# on_protoboard.net
KiCad netlist of a schematic drawn in EAGLE
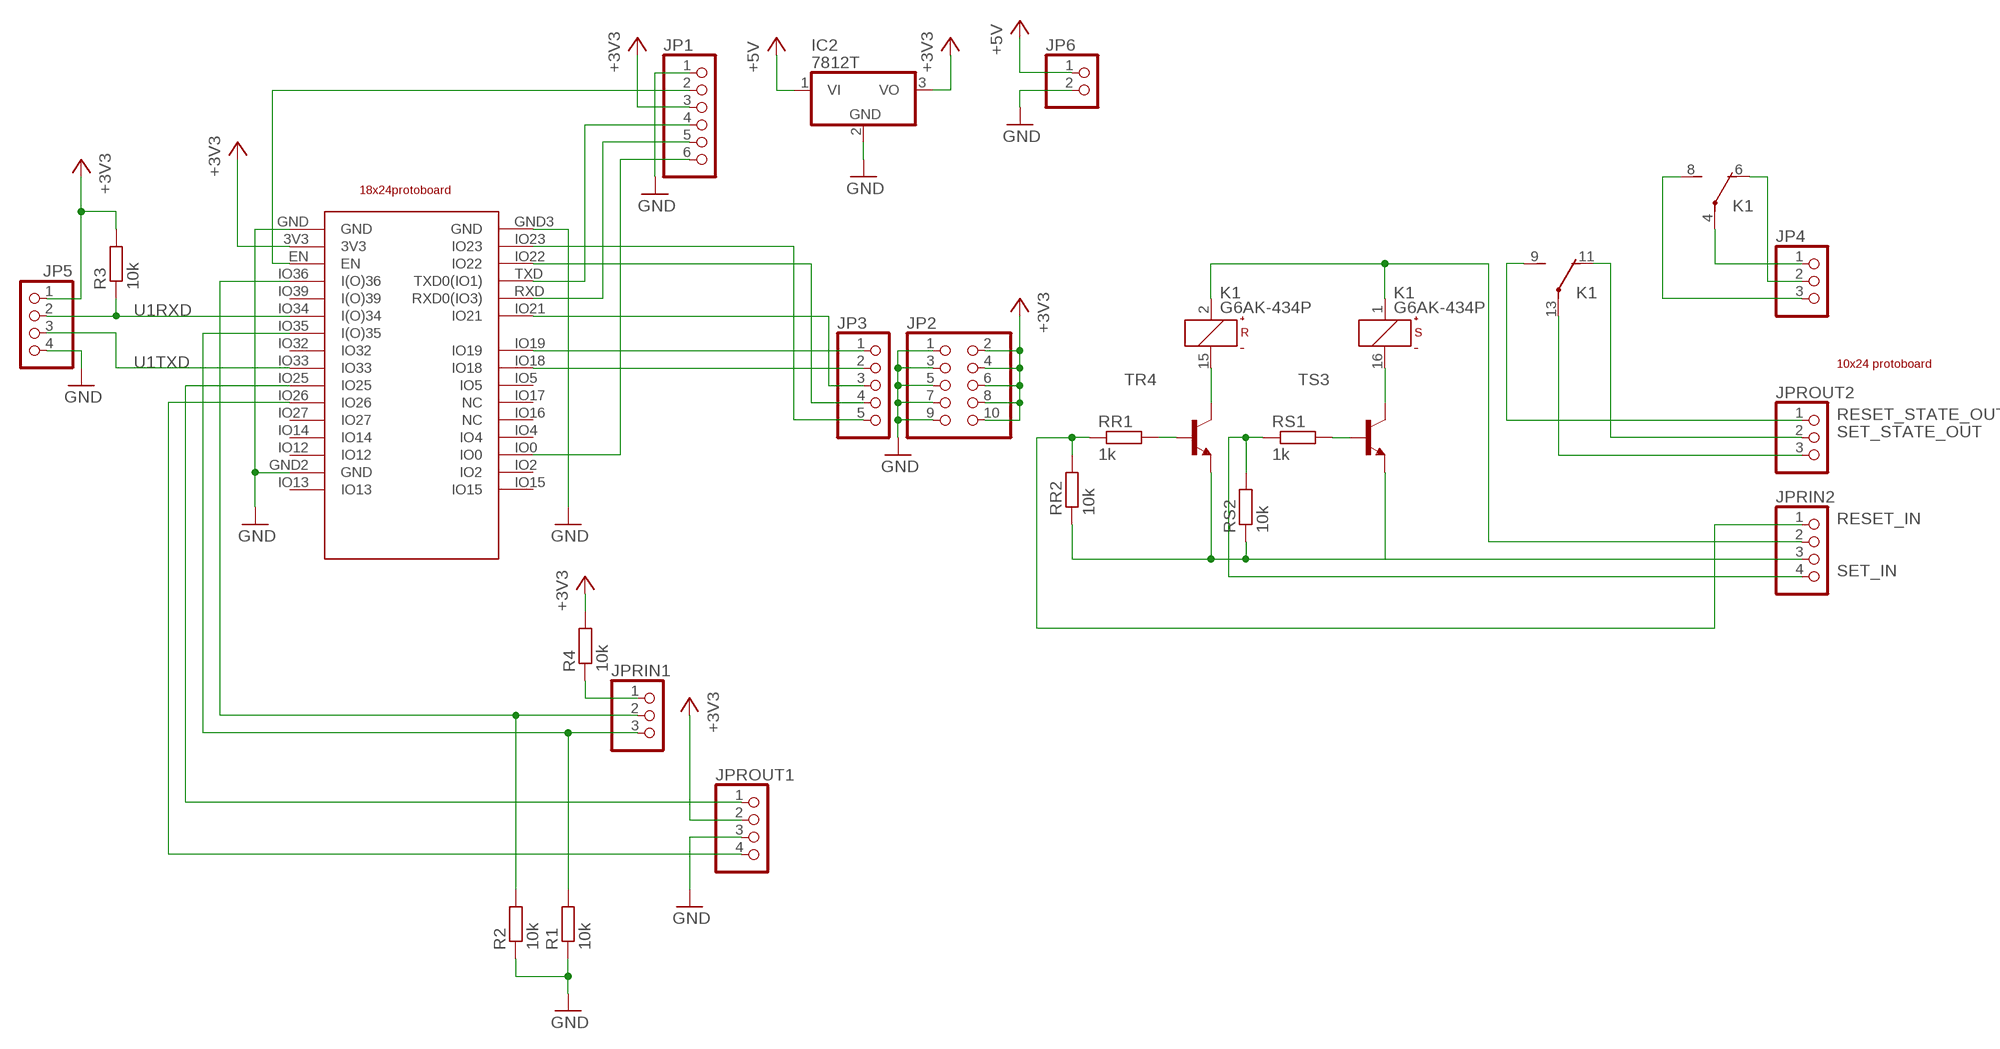
[diagram p0: schematic, sheet 1]

(export (version "E")
  (design (tool "Eeschema 10.0.6"))
  (components
    (comp (ref "ESP-32S-ADAPTER-PCB1")
      (value "ESP-32S-ADAPTER-BREAKOUT")
      (footprint "eagle-import:ESP-32S-ADAPTER-PCB")
      (libsource (lib "eagle-import") (part "ESP-32S-ADAPTER-BREAKOUT"))
    )
    (comp (ref "IC2")
      (value "7812T")
      (footprint "eagle-import:TO220H")
      (libsource (lib "eagle-import") (part "78T12"))
    )
    (comp (ref "JP1")
      (value "PINHD-1X6/90")
      (footprint "eagle-import:1X06_90")
      (libsource (lib "eagle-import") (part "PINHD-1X6/90"))
    )
    (comp (ref "JP2")
      (value "PINHD-2X5")
      (footprint "eagle-import:2X05")
      (libsource (lib "eagle-import") (part "PINHD-2X5"))
    )
    (comp (ref "JP3")
      (value "PINHD-1X5")
      (footprint "eagle-import:1X05")
      (libsource (lib "eagle-import") (part "PINHD-1X5"))
    )
    (comp (ref "JP4")
      (value "PINHD-1X3")
      (footprint "eagle-import:1X03")
      (libsource (lib "eagle-import") (part "PINHD-1X3"))
    )
    (comp (ref "JP5")
      (value "PINHD-1X4")
      (footprint "eagle-import:1X04")
      (libsource (lib "eagle-import") (part "PINHD-1X4"))
    )
    (comp (ref "JP6")
      (value "PINHD-1X2")
      (footprint "eagle-import:1X02")
      (libsource (lib "eagle-import") (part "PINHD-1X2"))
    )
    (comp (ref "JPRIN1")
      (value "PINHD-1X3")
      (footprint "eagle-import:1X03")
      (libsource (lib "eagle-import") (part "PINHD-1X3"))
    )
    (comp (ref "JPRIN2")
      (value "PINHD-1X4")
      (footprint "eagle-import:1X04")
      (libsource (lib "eagle-import") (part "PINHD-1X4"))
    )
    (comp (ref "JPROUT1")
      (value "PINHD-1X4")
      (footprint "eagle-import:1X04")
      (libsource (lib "eagle-import") (part "PINHD-1X4"))
    )
    (comp (ref "JPROUT2")
      (value "PINHD-1X3")
      (footprint "eagle-import:1X03")
      (libsource (lib "eagle-import") (part "PINHD-1X3"))
    )
    (comp (ref "K1")
      (value "G6AK-434P")
      (footprint "eagle-import:G6AK-434P")
      (libsource (lib "eagle-import") (part "G6AK-434P"))
    )
    (comp (ref "R1")
      (value "10k")
      (footprint "eagle-import:R0603")
      (libsource (lib "eagle-import") (part "R-EU_R0603"))
    )
    (comp (ref "R2")
      (value "10k")
      (footprint "eagle-import:R0603")
      (libsource (lib "eagle-import") (part "R-EU_R0603"))
    )
    (comp (ref "R3")
      (value "10k")
      (footprint "eagle-import:R0603")
      (libsource (lib "eagle-import") (part "R-EU_R0603"))
    )
    (comp (ref "R4")
      (value "10k")
      (footprint "eagle-import:R0603")
      (libsource (lib "eagle-import") (part "R-EU_R0603"))
    )
    (comp (ref "RR1")
      (value "1k")
      (footprint "eagle-import:R0603")
      (libsource (lib "eagle-import") (part "R-EU_R0603"))
    )
    (comp (ref "RR2")
      (value "10k")
      (footprint "eagle-import:R0603")
      (libsource (lib "eagle-import") (part "R-EU_R0603"))
    )
    (comp (ref "RS1")
      (value "1k")
      (footprint "eagle-import:R0603")
      (libsource (lib "eagle-import") (part "R-EU_R0603"))
    )
    (comp (ref "RS2")
      (value "10k")
      (footprint "eagle-import:R0603")
      (libsource (lib "eagle-import") (part "R-EU_R0603"))
    )
    (comp (ref "TR4")
      (value "-NPN-TO92-EBC")
      (footprint "eagle-import:TO92-EBC")
      (libsource (lib "eagle-import") (part "-NPN-TO92-EBC"))
    )
    (comp (ref "TS3")
      (value "-NPN-TO92-EBC")
      (footprint "eagle-import:TO92-EBC")
      (libsource (lib "eagle-import") (part "-NPN-TO92-EBC"))
    )
    (comp (ref "U$1")
      (value "18X24")
      (footprint "eagle-import:PROTOBOARD_18X24_HOLE")
      (libsource (lib "eagle-import") (part "18X24"))
    )
    (comp (ref "U$2")
      (value "10X24")
      (footprint "eagle-import:PROTOBOARD_10X24_HOLE")
      (libsource (lib "eagle-import") (part "10X24"))
    )
  )
  (nets
    (net (code "1") (name "+3V3") (class "Default")
      (node (ref "ESP-32S-ADAPTER-PCB1") (pin "3V3") (pinfunction "3V3_3V3") (pintype "bidirectional"))
      (node (ref "IC2") (pin "3") (pinfunction "VO_3") (pintype "passive"))
      (node (ref "JP1") (pin "3") (pinfunction "3_3") (pintype "passive"))
      (node (ref "JP2") (pin "10") (pinfunction "10_10") (pintype "passive"))
      (node (ref "JP2") (pin "2") (pinfunction "2_2") (pintype "passive"))
      (node (ref "JP2") (pin "4") (pinfunction "4_4") (pintype "passive"))
      (node (ref "JP2") (pin "6") (pinfunction "6_6") (pintype "passive"))
      (node (ref "JP2") (pin "8") (pinfunction "8_8") (pintype "passive"))
      (node (ref "JP5") (pin "1") (pinfunction "1_1") (pintype "passive"))
      (node (ref "JPROUT1") (pin "2") (pinfunction "2_2") (pintype "passive"))
      (node (ref "R3") (pin "2") (pinfunction "2_2") (pintype "passive"))
      (node (ref "R4") (pin "2") (pinfunction "2_2") (pintype "passive"))
    )
    (net (code "2") (name "+5V") (class "Default")
      (node (ref "IC2") (pin "1") (pinfunction "VI_1") (pintype "input"))
      (node (ref "JP6") (pin "1") (pinfunction "1_1") (pintype "passive"))
    )
    (net (code "3") (name "/RESET_IN") (class "Default")
      (node (ref "JPRIN2") (pin "1") (pinfunction "1_1") (pintype "passive"))
      (node (ref "RR1") (pin "1") (pinfunction "1_1") (pintype "passive"))
      (node (ref "RR2") (pin "2") (pinfunction "2_2") (pintype "passive"))
    )
    (net (code "4") (name "/RESET_STATE_OUT") (class "Default")
      (node (ref "JPROUT2") (pin "1") (pinfunction "1_1") (pintype "passive"))
      (node (ref "K1") (pin "9") (pinfunction "S_9") (pintype "passive"))
    )
    (net (code "5") (name "/SET_IN") (class "Default")
      (node (ref "JPRIN2") (pin "4") (pinfunction "4_4") (pintype "passive"))
      (node (ref "RS1") (pin "1") (pinfunction "1_1") (pintype "passive"))
      (node (ref "RS2") (pin "2") (pinfunction "2_2") (pintype "passive"))
    )
    (net (code "6") (name "/SET_STATE_OUT") (class "Default")
      (node (ref "JPROUT2") (pin "2") (pinfunction "2_2") (pintype "passive"))
      (node (ref "K1") (pin "11") (pinfunction "O_11") (pintype "passive"))
    )
    (net (code "7") (name "/U1RXD") (class "Default")
      (node (ref "ESP-32S-ADAPTER-PCB1") (pin "IO34") (pinfunction "I(O)34_IO34") (pintype "bidirectional"))
      (node (ref "JP5") (pin "2") (pinfunction "2_2") (pintype "passive"))
      (node (ref "R3") (pin "1") (pinfunction "1_1") (pintype "passive"))
    )
    (net (code "8") (name "/U1TXD") (class "Default")
      (node (ref "ESP-32S-ADAPTER-PCB1") (pin "IO33") (pinfunction "IO33_IO33") (pintype "bidirectional"))
      (node (ref "JP5") (pin "3") (pinfunction "3_3") (pintype "passive"))
    )
    (net (code "9") (name "GND") (class "Default")
      (node (ref "ESP-32S-ADAPTER-PCB1") (pin "GND") (pinfunction "GND_GND") (pintype "bidirectional"))
      (node (ref "ESP-32S-ADAPTER-PCB1") (pin "GND2") (pinfunction "GND_GND2") (pintype "bidirectional"))
      (node (ref "ESP-32S-ADAPTER-PCB1") (pin "GND3") (pinfunction "GND_GND3") (pintype "bidirectional"))
      (node (ref "IC2") (pin "2") (pinfunction "GND_2") (pintype "passive"))
      (node (ref "JP1") (pin "1") (pinfunction "1_1") (pintype "passive"))
      (node (ref "JP2") (pin "1") (pinfunction "1_1") (pintype "passive"))
      (node (ref "JP2") (pin "3") (pinfunction "3_3") (pintype "passive"))
      (node (ref "JP2") (pin "5") (pinfunction "5_5") (pintype "passive"))
      (node (ref "JP2") (pin "7") (pinfunction "7_7") (pintype "passive"))
      (node (ref "JP2") (pin "9") (pinfunction "9_9") (pintype "passive"))
      (node (ref "JP5") (pin "4") (pinfunction "4_4") (pintype "passive"))
      (node (ref "JP6") (pin "2") (pinfunction "2_2") (pintype "passive"))
      (node (ref "JPROUT1") (pin "3") (pinfunction "3_3") (pintype "passive"))
      (node (ref "R1") (pin "1") (pinfunction "1_1") (pintype "passive"))
      (node (ref "R2") (pin "1") (pinfunction "1_1") (pintype "passive"))
    )
    (net (code "10") (name "Net-(ESP-32S-ADAPTER-PCB1-I(O)35)") (class "Default")
      (node (ref "ESP-32S-ADAPTER-PCB1") (pin "IO35") (pinfunction "I(O)35_IO35") (pintype "bidirectional"))
      (node (ref "JPRIN1") (pin "3") (pinfunction "3_3") (pintype "passive"))
      (node (ref "R1") (pin "2") (pinfunction "2_2") (pintype "passive"))
    )
    (net (code "11") (name "Net-(ESP-32S-ADAPTER-PCB1-I(O)36)") (class "Default")
      (node (ref "ESP-32S-ADAPTER-PCB1") (pin "IO36") (pinfunction "I(O)36_IO36") (pintype "bidirectional"))
      (node (ref "JPRIN1") (pin "2") (pinfunction "2_2") (pintype "passive"))
      (node (ref "R2") (pin "2") (pinfunction "2_2") (pintype "passive"))
    )
    (net (code "12") (name "Net-(ESP-32S-ADAPTER-PCB1-PadEN)") (class "Default")
      (node (ref "ESP-32S-ADAPTER-PCB1") (pin "EN") (pinfunction "EN_EN") (pintype "bidirectional"))
      (node (ref "JP1") (pin "2") (pinfunction "2_2") (pintype "passive"))
    )
    (net (code "13") (name "Net-(ESP-32S-ADAPTER-PCB1-PadIO0)") (class "Default")
      (node (ref "ESP-32S-ADAPTER-PCB1") (pin "IO0") (pinfunction "IO0_IO0") (pintype "bidirectional"))
      (node (ref "JP1") (pin "6") (pinfunction "6_6") (pintype "passive"))
    )
    (net (code "14") (name "Net-(ESP-32S-ADAPTER-PCB1-PadIO18)") (class "Default")
      (node (ref "ESP-32S-ADAPTER-PCB1") (pin "IO18") (pinfunction "IO18_IO18") (pintype "bidirectional"))
      (node (ref "JP3") (pin "2") (pinfunction "2_2") (pintype "passive"))
    )
    (net (code "15") (name "Net-(ESP-32S-ADAPTER-PCB1-PadIO19)") (class "Default")
      (node (ref "ESP-32S-ADAPTER-PCB1") (pin "IO19") (pinfunction "IO19_IO19") (pintype "bidirectional"))
      (node (ref "JP3") (pin "1") (pinfunction "1_1") (pintype "passive"))
    )
    (net (code "16") (name "Net-(ESP-32S-ADAPTER-PCB1-PadIO21)") (class "Default")
      (node (ref "ESP-32S-ADAPTER-PCB1") (pin "IO21") (pinfunction "IO21_IO21") (pintype "bidirectional"))
      (node (ref "JP3") (pin "3") (pinfunction "3_3") (pintype "passive"))
    )
    (net (code "17") (name "Net-(ESP-32S-ADAPTER-PCB1-PadIO22)") (class "Default")
      (node (ref "ESP-32S-ADAPTER-PCB1") (pin "IO22") (pinfunction "IO22_IO22") (pintype "bidirectional"))
      (node (ref "JP3") (pin "4") (pinfunction "4_4") (pintype "passive"))
    )
    (net (code "18") (name "Net-(ESP-32S-ADAPTER-PCB1-PadIO23)") (class "Default")
      (node (ref "ESP-32S-ADAPTER-PCB1") (pin "IO23") (pinfunction "IO23_IO23") (pintype "bidirectional"))
      (node (ref "JP3") (pin "5") (pinfunction "5_5") (pintype "passive"))
    )
    (net (code "19") (name "Net-(ESP-32S-ADAPTER-PCB1-PadIO25)") (class "Default")
      (node (ref "ESP-32S-ADAPTER-PCB1") (pin "IO25") (pinfunction "IO25_IO25") (pintype "bidirectional"))
      (node (ref "JPROUT1") (pin "1") (pinfunction "1_1") (pintype "passive"))
    )
    (net (code "20") (name "Net-(ESP-32S-ADAPTER-PCB1-PadIO26)") (class "Default")
      (node (ref "ESP-32S-ADAPTER-PCB1") (pin "IO26") (pinfunction "IO26_IO26") (pintype "bidirectional"))
      (node (ref "JPROUT1") (pin "4") (pinfunction "4_4") (pintype "passive"))
    )
    (net (code "21") (name "Net-(ESP-32S-ADAPTER-PCB1-RXD0(IO3))") (class "Default")
      (node (ref "ESP-32S-ADAPTER-PCB1") (pin "RXD") (pinfunction "RXD0(IO3)_RXD") (pintype "bidirectional"))
      (node (ref "JP1") (pin "5") (pinfunction "5_5") (pintype "passive"))
    )
    (net (code "22") (name "Net-(ESP-32S-ADAPTER-PCB1-TXD0(IO1))") (class "Default")
      (node (ref "ESP-32S-ADAPTER-PCB1") (pin "TXD") (pinfunction "TXD0(IO1)_TXD") (pintype "bidirectional"))
      (node (ref "JP1") (pin "4") (pinfunction "4_4") (pintype "passive"))
    )
    (net (code "23") (name "Net-(JPRIN1-Pad1)") (class "Default")
      (node (ref "JPRIN1") (pin "1") (pinfunction "1_1") (pintype "passive"))
      (node (ref "R4") (pin "1") (pinfunction "1_1") (pintype "passive"))
    )
    (net (code "24") (name "Net-(JPRIN2-Pad3)") (class "Default")
      (node (ref "JPRIN2") (pin "3") (pinfunction "3_3") (pintype "passive"))
      (node (ref "RR2") (pin "1") (pinfunction "1_1") (pintype "passive"))
      (node (ref "RS2") (pin "1") (pinfunction "1_1") (pintype "passive"))
      (node (ref "TR4") (pin "E") (pinfunction "E_E") (pintype "passive"))
      (node (ref "TS3") (pin "E") (pinfunction "E_E") (pintype "passive"))
    )
    (net (code "25") (name "Net-(K1A-O)") (class "Default")
      (node (ref "JP4") (pin "2") (pinfunction "2_2") (pintype "passive"))
      (node (ref "K1") (pin "6") (pinfunction "O_6") (pintype "passive"))
    )
    (net (code "26") (name "Net-(K1A-P)") (class "Default")
      (node (ref "JP4") (pin "1") (pinfunction "1_1") (pintype "passive"))
      (node (ref "K1") (pin "4") (pinfunction "P_4") (pintype "passive"))
    )
    (net (code "27") (name "Net-(K1A-S)") (class "Default")
      (node (ref "JP4") (pin "3") (pinfunction "3_3") (pintype "passive"))
      (node (ref "K1") (pin "8") (pinfunction "S_8") (pintype "passive"))
    )
    (net (code "28") (name "Net-(K1B-P)") (class "Default")
      (node (ref "JPROUT2") (pin "3") (pinfunction "3_3") (pintype "passive"))
      (node (ref "K1") (pin "13") (pinfunction "P_13") (pintype "passive"))
    )
    (net (code "29") (name "Net-(K1E-+)") (class "Default")
      (node (ref "JPRIN2") (pin "2") (pinfunction "2_2") (pintype "passive"))
      (node (ref "K1") (pin "1") (pinfunction "+_1") (pintype "passive"))
      (node (ref "K1") (pin "2") (pinfunction "+_2") (pintype "passive"))
    )
    (net (code "30") (name "Net-(K1E--)") (class "Default")
      (node (ref "K1") (pin "15") (pinfunction "-_15") (pintype "passive"))
      (node (ref "TR4") (pin "C") (pinfunction "C_C") (pintype "passive"))
    )
    (net (code "31") (name "Net-(K1F--)") (class "Default")
      (node (ref "K1") (pin "16") (pinfunction "-_16") (pintype "passive"))
      (node (ref "TS3") (pin "C") (pinfunction "C_C") (pintype "passive"))
    )
    (net (code "32") (name "Net-(RR1-Pad2)") (class "Default")
      (node (ref "RR1") (pin "2") (pinfunction "2_2") (pintype "passive"))
      (node (ref "TR4") (pin "B") (pinfunction "B_B") (pintype "passive"))
    )
    (net (code "33") (name "Net-(RS1-Pad2)") (class "Default")
      (node (ref "RS1") (pin "2") (pinfunction "2_2") (pintype "passive"))
      (node (ref "TS3") (pin "B") (pinfunction "B_B") (pintype "passive"))
    )
    (net (code "34") (name "unconnected-(ESP-32S-ADAPTER-PCB1-I(O)39-PadIO39)") (class "Default")
      (node (ref "ESP-32S-ADAPTER-PCB1") (pin "IO39") (pinfunction "I(O)39_IO39") (pintype "bidirectional"))
    )
    (net (code "35") (name "unconnected-(ESP-32S-ADAPTER-PCB1-NC-PadIO16)") (class "Default")
      (node (ref "ESP-32S-ADAPTER-PCB1") (pin "IO16") (pinfunction "NC_IO16") (pintype "bidirectional"))
    )
    (net (code "36") (name "unconnected-(ESP-32S-ADAPTER-PCB1-NC-PadIO17)") (class "Default")
      (node (ref "ESP-32S-ADAPTER-PCB1") (pin "IO17") (pinfunction "NC_IO17") (pintype "bidirectional"))
    )
    (net (code "37") (name "unconnected-(ESP-32S-ADAPTER-PCB1-PadIO2)") (class "Default")
      (node (ref "ESP-32S-ADAPTER-PCB1") (pin "IO2") (pinfunction "IO2_IO2") (pintype "bidirectional"))
    )
    (net (code "38") (name "unconnected-(ESP-32S-ADAPTER-PCB1-PadIO4)") (class "Default")
      (node (ref "ESP-32S-ADAPTER-PCB1") (pin "IO4") (pinfunction "IO4_IO4") (pintype "bidirectional"))
    )
    (net (code "39") (name "unconnected-(ESP-32S-ADAPTER-PCB1-PadIO5)") (class "Default")
      (node (ref "ESP-32S-ADAPTER-PCB1") (pin "IO5") (pinfunction "IO5_IO5") (pintype "bidirectional"))
    )
    (net (code "40") (name "unconnected-(ESP-32S-ADAPTER-PCB1-PadIO12)") (class "Default")
      (node (ref "ESP-32S-ADAPTER-PCB1") (pin "IO12") (pinfunction "IO12_IO12") (pintype "bidirectional"))
    )
    (net (code "41") (name "unconnected-(ESP-32S-ADAPTER-PCB1-PadIO13)") (class "Default")
      (node (ref "ESP-32S-ADAPTER-PCB1") (pin "IO13") (pinfunction "IO13_IO13") (pintype "bidirectional"))
    )
    (net (code "42") (name "unconnected-(ESP-32S-ADAPTER-PCB1-PadIO14)") (class "Default")
      (node (ref "ESP-32S-ADAPTER-PCB1") (pin "IO14") (pinfunction "IO14_IO14") (pintype "bidirectional"))
    )
    (net (code "43") (name "unconnected-(ESP-32S-ADAPTER-PCB1-PadIO15)") (class "Default")
      (node (ref "ESP-32S-ADAPTER-PCB1") (pin "IO15") (pinfunction "IO15_IO15") (pintype "bidirectional"))
    )
    (net (code "44") (name "unconnected-(ESP-32S-ADAPTER-PCB1-PadIO27)") (class "Default")
      (node (ref "ESP-32S-ADAPTER-PCB1") (pin "IO27") (pinfunction "IO27_IO27") (pintype "bidirectional"))
    )
    (net (code "45") (name "unconnected-(ESP-32S-ADAPTER-PCB1-PadIO32)") (class "Default")
      (node (ref "ESP-32S-ADAPTER-PCB1") (pin "IO32") (pinfunction "IO32_IO32") (pintype "bidirectional"))
    )
  )
)
